# attiny84_rgb.net
KiCad netlist of a schematic drawn in EAGLE
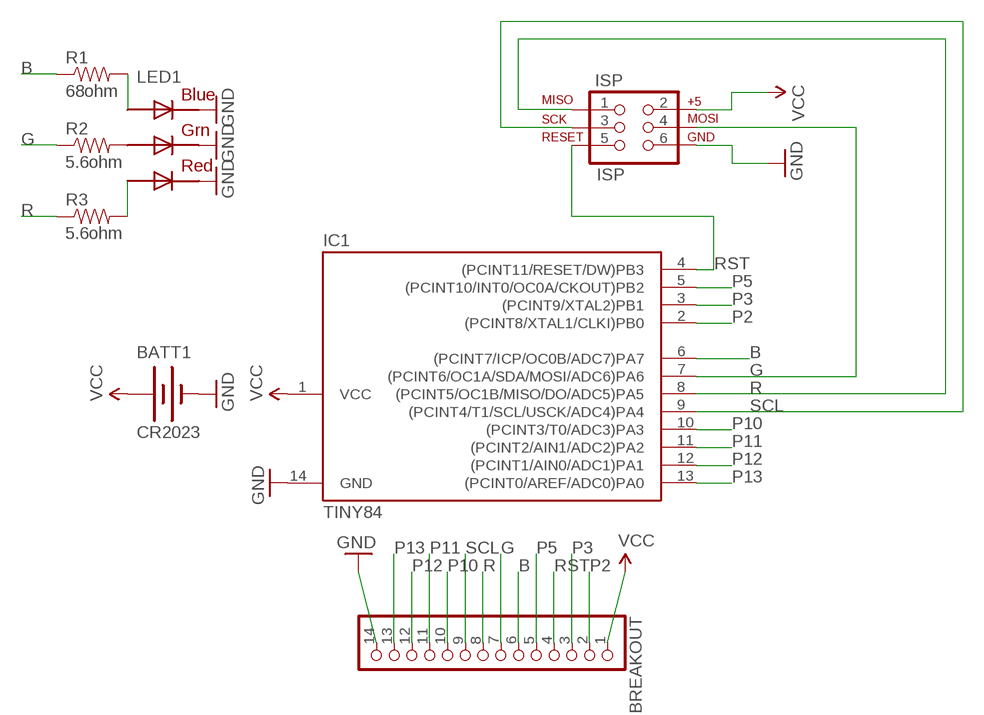
[diagram p0: schematic, sheet 1]

(export (version "E")
  (design (tool "Eeschema 10.0.6"))
  (components
    (comp (ref "BATT1")
      (value "CR2023")
      (footprint "eagle-import:BATTCON_12MM")
      (libsource (lib "eagle-import") (part "BATTERY12MM"))
    )
    (comp (ref "BREAKOUT")
      (value "PINHD-1X14")
      (footprint "eagle-import:1X14")
      (libsource (lib "eagle-import") (part "PINHD-1X14"))
    )
    (comp (ref "IC1")
      (value "TINY84")
      (footprint "eagle-import:SOIC14")
      (libsource (lib "eagle-import") (part "TINY24/44/84-SSU"))
    )
    (comp (ref "ISP")
      (value "ISP")
      (footprint "eagle-import:2X3-NS")
      (libsource (lib "eagle-import") (part "AVR_SPI_PRG_6NS"))
    )
    (comp (ref "LED1")
      (value "LED1")
      (footprint "eagle-import:RGBLED5050")
      (libsource (lib "eagle-import") (part "RGBLED5050"))
    )
    (comp (ref "R1")
      (value "68ohm")
      (footprint "eagle-import:1206")
      (libsource (lib "eagle-import") (part "RESISTOR1206"))
    )
    (comp (ref "R2")
      (value "5.6ohm")
      (footprint "eagle-import:1206")
      (libsource (lib "eagle-import") (part "RESISTOR1206"))
    )
    (comp (ref "R3")
      (value "5.6ohm")
      (footprint "eagle-import:1206")
      (libsource (lib "eagle-import") (part "RESISTOR1206"))
    )
  )
  (nets
    (net (code "1") (name "/B") (class "Default")
      (node (ref "BREAKOUT") (pin "6") (pinfunction "6_6") (pintype "passive"))
      (node (ref "IC1") (pin "6") (pinfunction "(PCINT7/ICP/OC0B/ADC7)PA7_6") (pintype "bidirectional"))
      (node (ref "R1") (pin "1") (pinfunction "1_1") (pintype "passive"))
    )
    (net (code "2") (name "/G") (class "Default")
      (node (ref "BREAKOUT") (pin "7") (pinfunction "7_7") (pintype "passive"))
      (node (ref "IC1") (pin "7") (pinfunction "(PCINT6/OC1A/SDA/MOSI/ADC6)PA6_7") (pintype "bidirectional"))
      (node (ref "ISP") (pin "4") (pinfunction "4_4") (pintype "passive"))
      (node (ref "R2") (pin "1") (pinfunction "1_1") (pintype "passive"))
    )
    (net (code "3") (name "/P2") (class "Default")
      (node (ref "BREAKOUT") (pin "2") (pinfunction "2_2") (pintype "passive"))
      (node (ref "IC1") (pin "2") (pinfunction "(PCINT8/XTAL1/CLKI)PB0_2") (pintype "bidirectional"))
    )
    (net (code "4") (name "/P3") (class "Default")
      (node (ref "BREAKOUT") (pin "3") (pinfunction "3_3") (pintype "passive"))
      (node (ref "IC1") (pin "3") (pinfunction "(PCINT9/XTAL2)PB1_3") (pintype "bidirectional"))
    )
    (net (code "5") (name "/P5") (class "Default")
      (node (ref "BREAKOUT") (pin "5") (pinfunction "5_5") (pintype "passive"))
      (node (ref "IC1") (pin "5") (pinfunction "(PCINT10/INT0/OC0A/CKOUT)PB2_5") (pintype "bidirectional"))
    )
    (net (code "6") (name "/P10") (class "Default")
      (node (ref "BREAKOUT") (pin "10") (pinfunction "10_10") (pintype "passive"))
      (node (ref "IC1") (pin "10") (pinfunction "(PCINT3/T0/ADC3)PA3_10") (pintype "bidirectional"))
    )
    (net (code "7") (name "/P11") (class "Default")
      (node (ref "BREAKOUT") (pin "11") (pinfunction "11_11") (pintype "passive"))
      (node (ref "IC1") (pin "11") (pinfunction "(PCINT2/AIN1/ADC2)PA2_11") (pintype "bidirectional"))
    )
    (net (code "8") (name "/P12") (class "Default")
      (node (ref "BREAKOUT") (pin "12") (pinfunction "12_12") (pintype "passive"))
      (node (ref "IC1") (pin "12") (pinfunction "(PCINT1/AIN0/ADC1)PA1_12") (pintype "bidirectional"))
    )
    (net (code "9") (name "/P13") (class "Default")
      (node (ref "BREAKOUT") (pin "13") (pinfunction "13_13") (pintype "passive"))
      (node (ref "IC1") (pin "13") (pinfunction "(PCINT0/AREF/ADC0)PA0_13") (pintype "bidirectional"))
    )
    (net (code "10") (name "/R") (class "Default")
      (node (ref "BREAKOUT") (pin "8") (pinfunction "8_8") (pintype "passive"))
      (node (ref "IC1") (pin "8") (pinfunction "(PCINT5/OC1B/MISO/DO/ADC5)PA5_8") (pintype "bidirectional"))
      (node (ref "ISP") (pin "1") (pinfunction "1_1") (pintype "passive"))
      (node (ref "R3") (pin "1") (pinfunction "1_1") (pintype "passive"))
    )
    (net (code "11") (name "/RST") (class "Default")
      (node (ref "BREAKOUT") (pin "4") (pinfunction "4_4") (pintype "passive"))
      (node (ref "IC1") (pin "4") (pinfunction "(PCINT11/RESET/DW)PB3_4") (pintype "bidirectional"))
      (node (ref "ISP") (pin "5") (pinfunction "5_5") (pintype "passive"))
    )
    (net (code "12") (name "/SCL") (class "Default")
      (node (ref "BREAKOUT") (pin "9") (pinfunction "9_9") (pintype "passive"))
      (node (ref "IC1") (pin "9") (pinfunction "(PCINT4/T1/SCL/USCK/ADC4)PA4_9") (pintype "bidirectional"))
      (node (ref "ISP") (pin "3") (pinfunction "3_3") (pintype "passive"))
    )
    (net (code "13") (name "GND") (class "Default")
      (node (ref "BATT1") (pin "GND") (pinfunction "-_GND") (pintype "power_in"))
      (node (ref "BREAKOUT") (pin "14") (pinfunction "14_14") (pintype "passive"))
      (node (ref "IC1") (pin "14") (pinfunction "GND_14") (pintype "power_in"))
      (node (ref "ISP") (pin "6") (pinfunction "6_6") (pintype "passive"))
      (node (ref "LED1") (pin "4") (pinfunction "BLUE_C_4") (pintype "bidirectional"))
      (node (ref "LED1") (pin "5") (pinfunction "RED_C_5") (pintype "bidirectional"))
      (node (ref "LED1") (pin "6") (pinfunction "GREEN_C_6") (pintype "bidirectional"))
    )
    (net (code "14") (name "Net-(LED1-BLUE_A)") (class "Default")
      (node (ref "LED1") (pin "3") (pinfunction "BLUE_A_3") (pintype "bidirectional"))
      (node (ref "R1") (pin "2") (pinfunction "2_2") (pintype "passive"))
    )
    (net (code "15") (name "Net-(LED1-GREEN_A)") (class "Default")
      (node (ref "LED1") (pin "1") (pinfunction "GREEN_A_1") (pintype "bidirectional"))
      (node (ref "R2") (pin "2") (pinfunction "2_2") (pintype "passive"))
    )
    (net (code "16") (name "Net-(LED1-RED_A)") (class "Default")
      (node (ref "LED1") (pin "2") (pinfunction "RED_A_2") (pintype "bidirectional"))
      (node (ref "R3") (pin "2") (pinfunction "2_2") (pintype "passive"))
    )
    (net (code "17") (name "VCC") (class "Default")
      (node (ref "BATT1") (pin "PWR@1") (pinfunction "+_PWR@1") (pintype "power_in"))
      (node (ref "BREAKOUT") (pin "1") (pinfunction "1_1") (pintype "passive"))
      (node (ref "IC1") (pin "1") (pinfunction "VCC_1") (pintype "power_in"))
      (node (ref "ISP") (pin "2") (pinfunction "2_2") (pintype "passive"))
    )
  )
)
